# webench_design_4015146_2_ad14_sim.net
KiCad netlist of a schematic drawn in Altium Designer
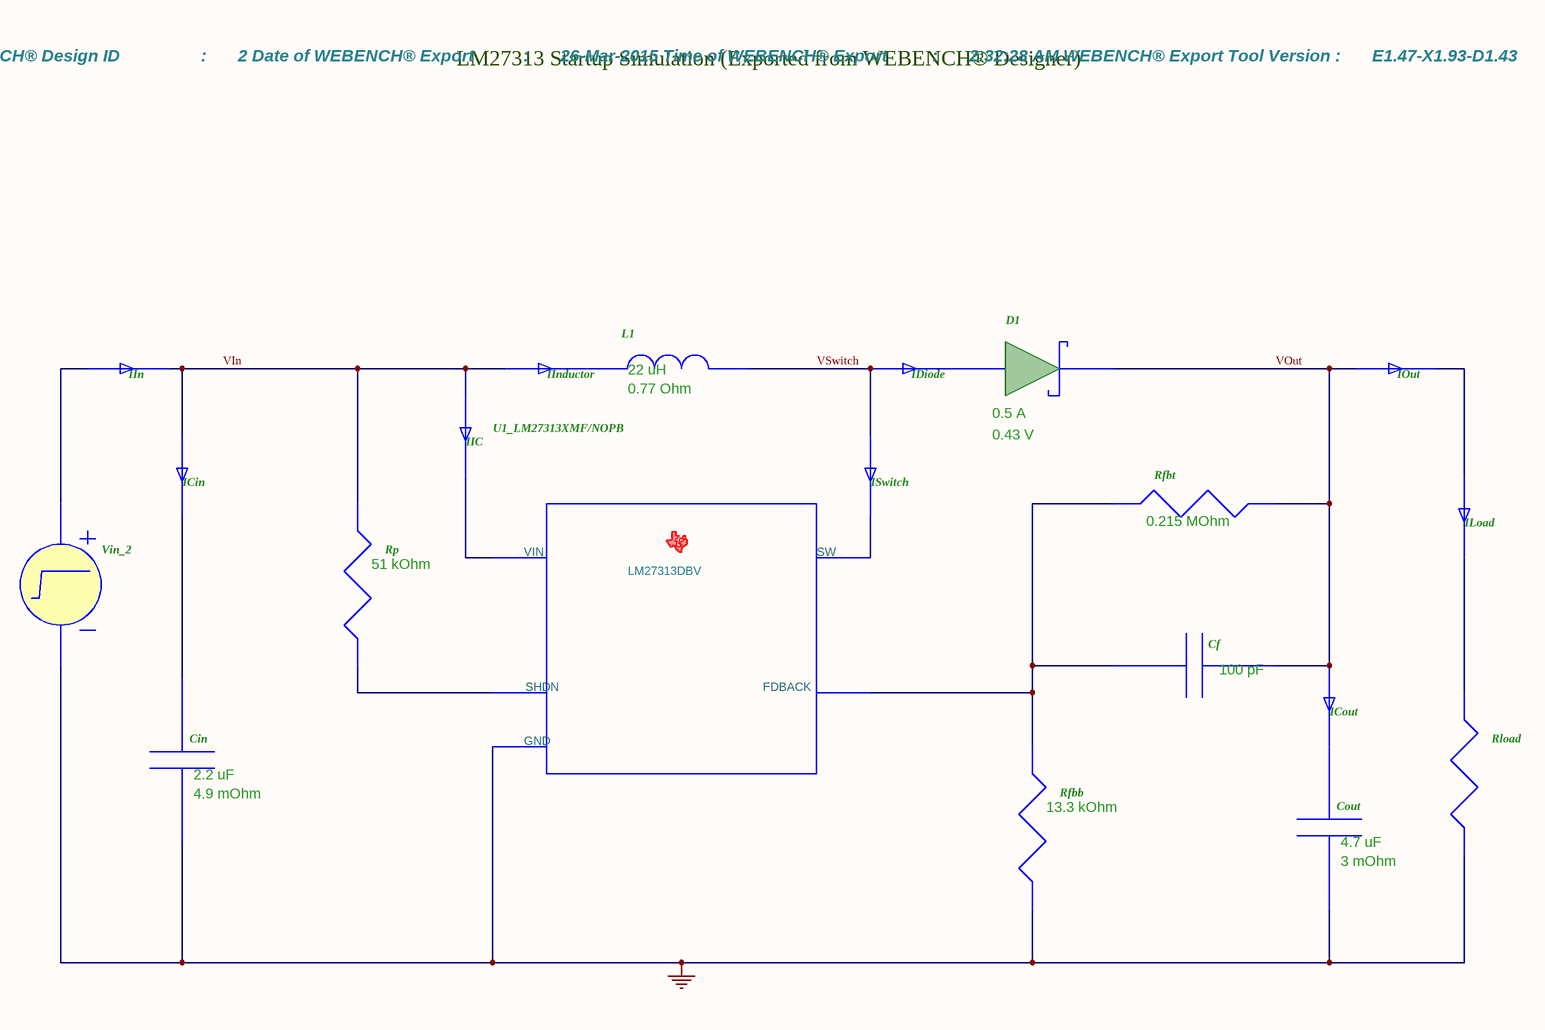
[diagram p0: webench_design_4015146_2_ad14_sim.SchDoc]

(export (version "E")
  (design (tool "Eeschema 10.0.6"))
  (components
    (comp (ref "Cf") (value "~") (libsource (lib "*") (part "Cf")))
    (comp (ref "Cin") (value "~") (libsource (lib "*") (part "Cin")))
    (comp (ref "Cout") (value "~") (libsource (lib "*") (part "Cout")))
    (comp (ref "D1") (value "~") (libsource (lib "*") (part "D1")))
    (comp (ref "ICin") (value "~") (libsource (lib "*") (part "ICin")))
    (comp (ref "ICout") (value "~") (libsource (lib "*") (part "ICout")))
    (comp (ref "IDiode") (value "~") (libsource (lib "*") (part "IDiode")))
    (comp (ref "IIC") (value "~") (libsource (lib "*") (part "IIC")))
    (comp (ref "IIn") (value "~") (libsource (lib "*") (part "IIn")))
    (comp (ref "IInductor") (value "~") (libsource (lib "*") (part "IInductor")))
    (comp (ref "ILoad") (value "~") (libsource (lib "*") (part "ILoad")))
    (comp (ref "IOut") (value "~") (libsource (lib "*") (part "IOut")))
    (comp (ref "ISwitch") (value "~") (libsource (lib "*") (part "ISwitch")))
    (comp (ref "L1") (value "~") (libsource (lib "*") (part "L1")))
    (comp (ref "Rfbb") (value "~") (libsource (lib "*") (part "Rfbb")))
    (comp (ref "Rfbt") (value "~") (libsource (lib "*") (part "Rfbt")))
    (comp (ref "Rload") (value "~") (libsource (lib "*") (part "Rload")))
    (comp (ref "Rp") (value "~") (libsource (lib "*") (part "Rp")))
    (comp (ref "U1_LM27313XMF/NOPB") (value "~") (libsource (lib "*") (part "U1_LM27313XMF/NOPB")))
    (comp (ref "Vin_2") (value "~") (libsource (lib "*") (part "Vin_2")))
  )
  (nets
    (net (code "1") (name "/VIn") (class "Default")
      (node (ref "ICin") (pin "2") (pinfunction "2_2") (pintype "passive"))
      (node (ref "IIC") (pin "2") (pinfunction "2_2") (pintype "passive"))
      (node (ref "IIn") (pin "2") (pinfunction "2_2") (pintype "passive"))
      (node (ref "IInductor") (pin "1") (pinfunction "1_1") (pintype "passive"))
      (node (ref "Rp") (pin "1") (pinfunction "1_1") (pintype "passive"))
    )
    (net (code "2") (name "/VOut") (class "Default")
      (node (ref "Cf") (pin "6") (pinfunction "6_6") (pintype "passive"))
      (node (ref "D1") (pin "K") (pinfunction "K_K") (pintype "passive"))
      (node (ref "ICout") (pin "2") (pinfunction "2_2") (pintype "passive"))
      (node (ref "IOut") (pin "1") (pinfunction "1_1") (pintype "passive"))
      (node (ref "Rfbt") (pin "6") (pinfunction "6_6") (pintype "passive"))
    )
    (net (code "3") (name "/VSwitch") (class "Default")
      (node (ref "IDiode") (pin "1") (pinfunction "1_1") (pintype "passive"))
      (node (ref "ISwitch") (pin "2") (pinfunction "2_2") (pintype "passive"))
      (node (ref "L1") (pin "2") (pinfunction "2_2") (pintype "passive"))
    )
    (net (code "4") (name "GND") (class "Default")
      (node (ref "Cin") (pin "2") (pinfunction "2_2") (pintype "passive"))
      (node (ref "Cout") (pin "4") (pinfunction "4_4") (pintype "passive"))
      (node (ref "Rfbb") (pin "0") (pinfunction "0_0") (pintype "passive"))
      (node (ref "Rload") (pin "2") (pinfunction "2_2") (pintype "passive"))
      (node (ref "U1_LM27313XMF/NOPB") (pin "GND") (pinfunction "GND_GND") (pintype "passive"))
      (node (ref "Vin_2") (pin "2") (pinfunction "2_2") (pintype "passive"))
    )
    (net (code "5") (name "Net-(Cf-Pad5)") (class "Default")
      (node (ref "Cf") (pin "5") (pinfunction "5_5") (pintype "passive"))
      (node (ref "Rfbb") (pin "5") (pinfunction "5_5") (pintype "passive"))
      (node (ref "Rfbt") (pin "5") (pinfunction "5_5") (pintype "passive"))
      (node (ref "U1_LM27313XMF/NOPB") (pin "FDBACK") (pinfunction "FDBACK_FDBACK") (pintype "passive"))
    )
    (net (code "6") (name "Net-(Cin-Pad1)") (class "Default")
      (node (ref "Cin") (pin "1") (pinfunction "1_1") (pintype "passive"))
      (node (ref "ICin") (pin "1") (pinfunction "1_1") (pintype "passive"))
    )
    (net (code "7") (name "Net-(Cout-Pad2)") (class "Default")
      (node (ref "Cout") (pin "2") (pinfunction "2_2") (pintype "passive"))
      (node (ref "ICout") (pin "1") (pinfunction "1_1") (pintype "passive"))
    )
    (net (code "8") (name "Net-(D1-PadA)") (class "Default")
      (node (ref "D1") (pin "A") (pinfunction "A_A") (pintype "passive"))
      (node (ref "IDiode") (pin "2") (pinfunction "2_2") (pintype "passive"))
    )
    (net (code "9") (name "Net-(IIC-Pad1)") (class "Default")
      (node (ref "IIC") (pin "1") (pinfunction "1_1") (pintype "passive"))
      (node (ref "U1_LM27313XMF/NOPB") (pin "VIN") (pinfunction "VIN_VIN") (pintype "passive"))
    )
    (net (code "10") (name "Net-(IIn-Pad1)") (class "Default")
      (node (ref "IIn") (pin "1") (pinfunction "1_1") (pintype "passive"))
      (node (ref "Vin_2") (pin "1") (pinfunction "1_1") (pintype "passive"))
    )
    (net (code "11") (name "Net-(IInductor-Pad2)") (class "Default")
      (node (ref "IInductor") (pin "2") (pinfunction "2_2") (pintype "passive"))
      (node (ref "L1") (pin "1") (pinfunction "1_1") (pintype "passive"))
    )
    (net (code "12") (name "Net-(ILoad-Pad1)") (class "Default")
      (node (ref "ILoad") (pin "1") (pinfunction "1_1") (pintype "passive"))
      (node (ref "Rload") (pin "1") (pinfunction "1_1") (pintype "passive"))
    )
    (net (code "13") (name "Net-(ILoad-Pad2)") (class "Default")
      (node (ref "ILoad") (pin "2") (pinfunction "2_2") (pintype "passive"))
      (node (ref "IOut") (pin "2") (pinfunction "2_2") (pintype "passive"))
    )
    (net (code "14") (name "Net-(ISwitch-Pad1)") (class "Default")
      (node (ref "ISwitch") (pin "1") (pinfunction "1_1") (pintype "passive"))
      (node (ref "U1_LM27313XMF/NOPB") (pin "SW") (pinfunction "SW_SW") (pintype "passive"))
    )
    (net (code "15") (name "Net-(Rp-Pad2)") (class "Default")
      (node (ref "Rp") (pin "2") (pinfunction "2_2") (pintype "passive"))
      (node (ref "U1_LM27313XMF/NOPB") (pin "SHDN") (pinfunction "SHDN_SHDN") (pintype "passive"))
    )
  )
)
